# Sheet8.net
KiCad netlist of a schematic drawn in Altium Designer
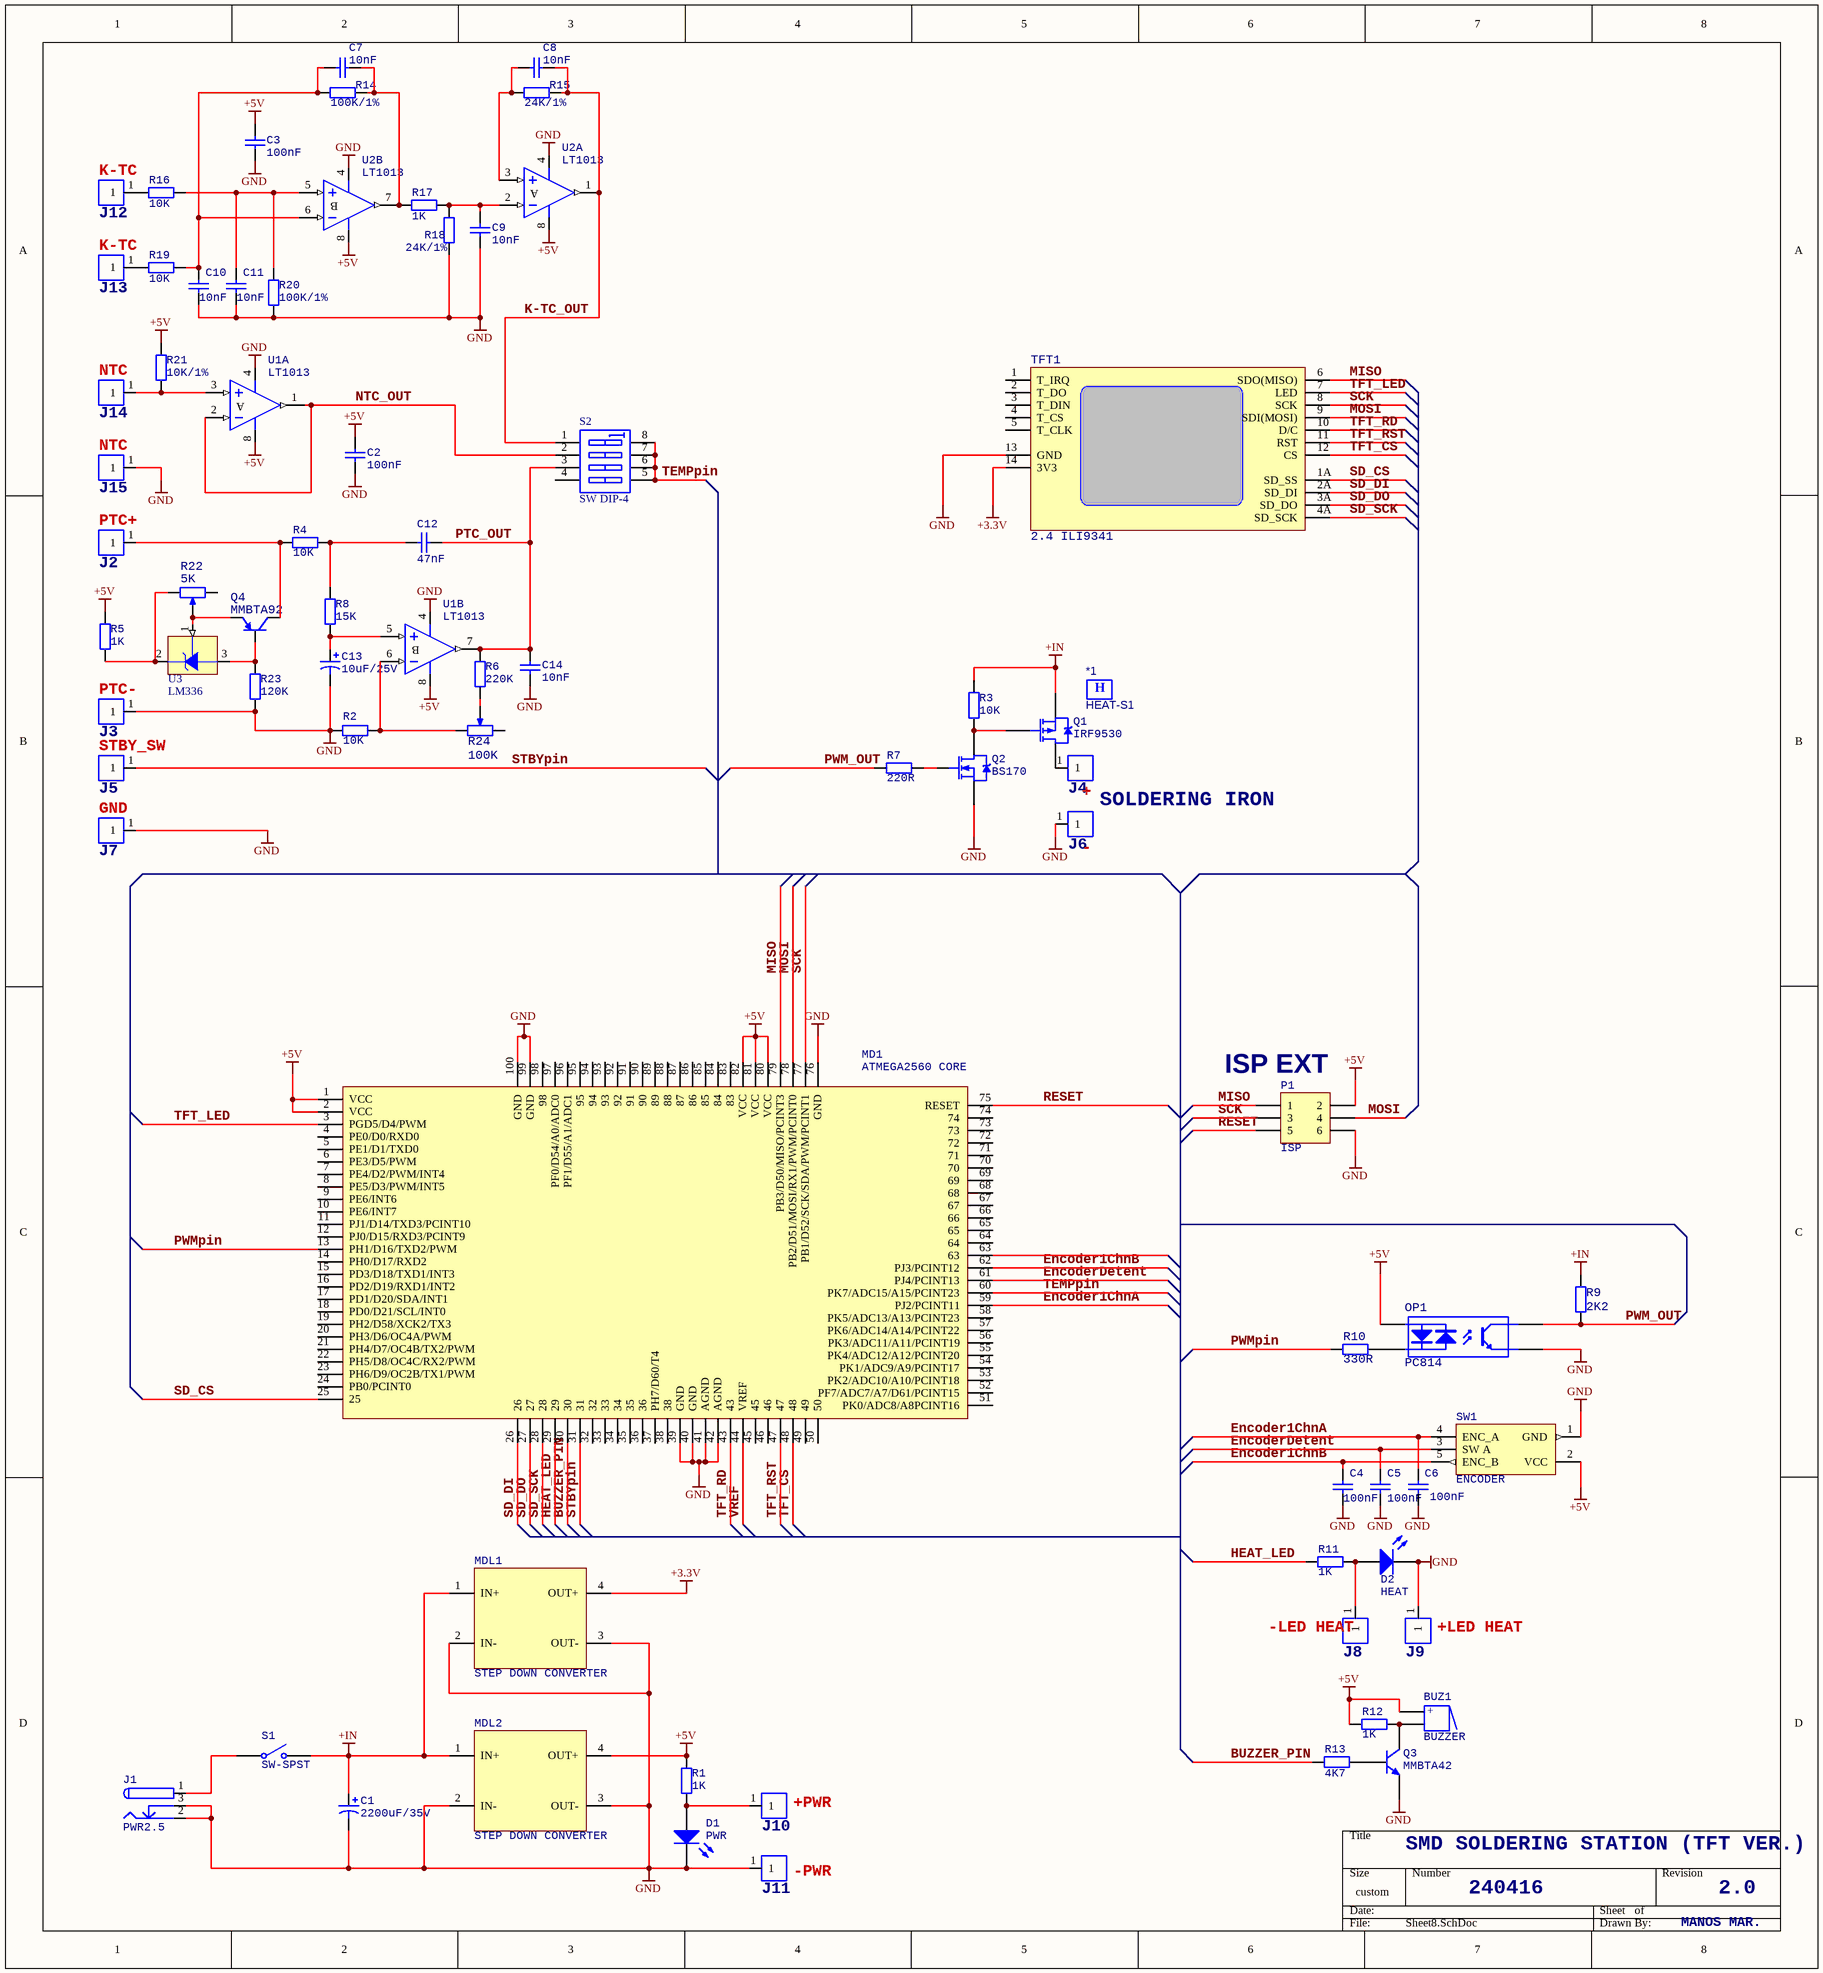
[diagram p0: Sheet8.SchDoc]

(export (version "E")
  (design (tool "Eeschema 10.0.6"))
  (components
    (comp (ref "*1")
      (value "HEAT-S1")
      (footprint "SK 104 HEATSHINK")
      (libsource (lib "SG_INTLIB") (part "HEAT-S1"))
    )
    (comp (ref "BUZ1") (value "BUZZER") (footprint "BUZZER") (libsource (lib "SMD STATION") (part "BUZZER")))
    (comp (ref "C1")
      (value "2200uF/35V")
      (footprint "RB5-10.5")
      (description "Polarized Capacitor (Radial)")
      (fields (field (name "PUBLISHER") "Altium Limited"))
      (libsource (lib "Miscellaneous Devices") (part "Cap Pol1"))
    )
    (comp (ref "C2")
      (value "100nF")
      (footprint "0805")
      (description "Capacitor, Ceramic, 4.7uF 10% 16V 0805 (2012) X7R")
      (fields (field (name "TOLERANCE") "10 %"))
      (libsource (lib "AltiumDesignLibrary") (part "CAP-NP"))
    )
    (comp (ref "C3")
      (value "100nF")
      (footprint "0805")
      (description "Capacitor, Ceramic, 4.7uF 10% 16V 0805 (2012) X7R")
      (fields (field (name "TOLERANCE") "10 %"))
      (libsource (lib "AltiumDesignLibrary") (part "CAP-NP"))
    )
    (comp (ref "C4")
      (value "100nF")
      (footprint "0805")
      (description "Capacitor")
      (fields (field (name "PUBLISHER") "Altium Limited"))
      (libsource (lib "Miscellaneous Devices") (part "Cap"))
    )
    (comp (ref "C5")
      (value "100nF")
      (footprint "0805")
      (description "Capacitor")
      (fields (field (name "PUBLISHER") "Altium Limited"))
      (libsource (lib "Miscellaneous Devices") (part "Cap"))
    )
    (comp (ref "C6")
      (value "100nF")
      (footprint "0805")
      (description "Capacitor")
      (fields (field (name "PUBLISHER") "Altium Limited"))
      (libsource (lib "Miscellaneous Devices") (part "Cap"))
    )
    (comp (ref "C7")
      (value "10nF")
      (footprint "0805")
      (description "Capacitor, Ceramic, 4.7uF 10% 16V 0805 (2012) X7R")
      (fields (field (name "TOLERANCE") "10 %"))
      (libsource (lib "AltiumDesignLibrary") (part "CAP-NP"))
    )
    (comp (ref "C8")
      (value "10nF")
      (footprint "0805")
      (description "Capacitor, Ceramic, 4.7uF 10% 16V 0805 (2012) X7R")
      (fields (field (name "TOLERANCE") "10 %"))
      (libsource (lib "AltiumDesignLibrary") (part "CAP-NP"))
    )
    (comp (ref "C9")
      (value "10nF")
      (footprint "0805")
      (description "Capacitor, Ceramic, 4.7uF 10% 16V 0805 (2012) X7R")
      (fields (field (name "TOLERANCE") "10 %"))
      (libsource (lib "AltiumDesignLibrary") (part "CAP-NP"))
    )
    (comp (ref "C10")
      (value "10nF")
      (footprint "0805")
      (description "Capacitor, Ceramic, 4.7uF 10% 16V 0805 (2012) X7R")
      (fields (field (name "TOLERANCE") "10 %"))
      (libsource (lib "AltiumDesignLibrary") (part "CAP-NP"))
    )
    (comp (ref "C11")
      (value "10nF")
      (footprint "0805")
      (description "Capacitor, Ceramic, 4.7uF 10% 16V 0805 (2012) X7R")
      (fields (field (name "TOLERANCE") "10 %"))
      (libsource (lib "AltiumDesignLibrary") (part "CAP-NP"))
    )
    (comp (ref "C12")
      (value "47nF")
      (footprint "0805")
      (description "Capacitor, Ceramic, 4.7uF 10% 16V 0805 (2012) X7R")
      (fields (field (name "TOLERANCE") "10 %"))
      (libsource (lib "AltiumDesignLibrary") (part "CAP-NP"))
    )
    (comp (ref "C13")
      (value "10uF/25V")
      (footprint "RB-08")
      (description "Polarized Capacitor (Radial)")
      (fields (field (name "PUBLISHER") "Altium Limited"))
      (libsource (lib "Miscellaneous Devices") (part "Cap Pol1"))
    )
    (comp (ref "C14")
      (value "10nF")
      (footprint "0805")
      (description "Capacitor, Ceramic, 4.7uF 10% 16V 0805 (2012) X7R")
      (fields (field (name "TOLERANCE") "10 %"))
      (libsource (lib "AltiumDesignLibrary") (part "CAP-NP"))
    )
    (comp (ref "D1")
      (value "PWR")
      (footprint "1206D")
      (description "Typical INFRARED GaAs LED")
      (fields (field (name "PUBLISHER") "Altium Limited"))
      (libsource (lib "Miscellaneous Devices") (part "LED0"))
    )
    (comp (ref "D2")
      (value "HEAT")
      (footprint "1206D")
      (description "Typical INFRARED GaAs LED")
      (fields (field (name "PUBLISHER") "Altium Limited"))
      (libsource (lib "Miscellaneous Devices") (part "LED0"))
    )
    (comp (ref "J1")
      (value "PWR2.5")
      (footprint "POWER JACK")
      (description "Low Voltage Power Supply Connector")
      (fields (field (name "PUBLISHER") "Altium Limited"))
      (libsource (lib "Miscellaneous Connectors") (part "PWR2.5"))
    )
    (comp (ref "J2")
      (value "PTC+")
      (footprint "CON2")
      (fields (field (name "MANUFACTURER") "Sta.Ge HELLAS"))
      (libsource (lib "Z_General_SCH_Library") (part "CON1_S"))
    )
    (comp (ref "J3")
      (value "PTC-")
      (footprint "CON2")
      (fields (field (name "MANUFACTURER") "Sta.Ge HELLAS"))
      (libsource (lib "Z_General_SCH_Library") (part "CON1_S"))
    )
    (comp (ref "J4")
      (value "+")
      (footprint "CON2")
      (fields (field (name "MANUFACTURER") "Sta.Ge HELLAS"))
      (libsource (lib "") (part "CON1_S_1"))
    )
    (comp (ref "J5")
      (value "STBY_SW")
      (footprint "CON2")
      (fields (field (name "MANUFACTURER") "Sta.Ge HELLAS"))
      (libsource (lib "Z_General_SCH_Library") (part "CON1_S"))
    )
    (comp (ref "J6")
      (value "-")
      (footprint "CON2")
      (fields (field (name "MANUFACTURER") "Sta.Ge HELLAS"))
      (libsource (lib "") (part "CON1_S_1"))
    )
    (comp (ref "J7")
      (value "GND")
      (footprint "CON2")
      (fields (field (name "MANUFACTURER") "Sta.Ge HELLAS"))
      (libsource (lib "Z_General_SCH_Library") (part "CON1_S"))
    )
    (comp (ref "J8")
      (value "-LED HEAT")
      (footprint "CON2")
      (fields (field (name "MANUFACTURER") "Sta.Ge HELLAS"))
      (libsource (lib "") (part "CON1_S_2"))
    )
    (comp (ref "J9")
      (value "+LED HEAT")
      (footprint "CON2")
      (fields (field (name "MANUFACTURER") "Sta.Ge HELLAS"))
      (libsource (lib "") (part "CON1_S_2"))
    )
    (comp (ref "J10")
      (value "+PWR")
      (footprint "CON2")
      (fields (field (name "MANUFACTURER") "Sta.Ge HELLAS"))
      (libsource (lib "") (part "CON1_S_1"))
    )
    (comp (ref "J11")
      (value "-PWR")
      (footprint "CON2")
      (fields (field (name "MANUFACTURER") "Sta.Ge HELLAS"))
      (libsource (lib "") (part "CON1_S_1"))
    )
    (comp (ref "J12")
      (value "K-TC")
      (footprint "CON2")
      (fields (field (name "MANUFACTURER") "Sta.Ge HELLAS"))
      (libsource (lib "Z_General_SCH_Library") (part "CON1_S"))
    )
    (comp (ref "J13")
      (value "K-TC")
      (footprint "CON2")
      (fields (field (name "MANUFACTURER") "Sta.Ge HELLAS"))
      (libsource (lib "Z_General_SCH_Library") (part "CON1_S"))
    )
    (comp (ref "J14")
      (value "NTC")
      (footprint "CON2")
      (fields (field (name "MANUFACTURER") "Sta.Ge HELLAS"))
      (libsource (lib "Z_General_SCH_Library") (part "CON1_S"))
    )
    (comp (ref "J15")
      (value "NTC")
      (footprint "CON2")
      (fields (field (name "MANUFACTURER") "Sta.Ge HELLAS"))
      (libsource (lib "Z_General_SCH_Library") (part "CON1_S"))
    )
    (comp (ref "MD1")
      (value "ATMEGA2560 CORE")
      (footprint "ATMEGA 2560 CORE")
      (libsource (lib "SMD STATION") (part "ATMEGA2560 CORE"))
    )
    (comp (ref "MDL1")
      (value "STEP DOWN CONVERTER")
      (footprint "STEP DOWN CONVERTER MINI")
      (libsource (lib "SMD STATION") (part "STEP DOWN CONVERTER"))
    )
    (comp (ref "MDL2")
      (value "STEP DOWN CONVERTER")
      (footprint "STEP DOWN CONVERTER MINI")
      (libsource (lib "SMD STATION") (part "STEP DOWN CONVERTER"))
    )
    (comp (ref "OP1")
      (value "PC814")
      (footprint "SOP-4")
      (description "AC OPTOCUPLER")
      (libsource (lib "STAGE_MP3") (part "OPTO-AC1"))
    )
    (comp (ref "P1")
      (value "ISP")
      (footprint "HDR2X3")
      (description "Header, 3-Pin, Dual row")
      (fields (field (name "PUBLISHER") "Altium Limited"))
      (libsource (lib "Miscellaneous Connectors") (part "Header 3X2"))
    )
    (comp (ref "Q1")
      (value "IRF9530")
      (footprint "TO-220V")
      (description "P-Channel Power MOSFET")
      (fields (field (name "PUBLISHER") "Altium Limited"))
      (libsource (lib "Miscellaneous Devices") (part "PMOS-2"))
    )
    (comp (ref "Q2")
      (value "BS170")
      (footprint "T0-92")
      (description "N-Channel Power MOSFET")
      (fields (field (name "PUBLISHER") "Altium Limited"))
      (libsource (lib "Miscellaneous Devices") (part "NMOS-2"))
    )
    (comp (ref "Q3")
      (value "MMBTA42")
      (footprint "SO-G3")
      (description "NPN Bipolar Transistor")
      (fields (field (name "PUBLISHER") "Altium Limited"))
      (libsource (lib "Miscellaneous Devices") (part "NPN"))
    )
    (comp (ref "Q4")
      (value "MMBTA92")
      (footprint "SO-G3")
      (description "PNP Bipolar Transistor")
      (fields (field (name "PUBLISHER") "Altium Limited"))
      (libsource (lib "Miscellaneous Devices") (part "PNP"))
    )
    (comp (ref "R1")
      (value "1K")
      (footprint "0805")
      (description "Resistor")
      (fields (field (name "PUBLISHER") "Altium Limited"))
      (libsource (lib "") (part "Res2_1"))
    )
    (comp (ref "R2")
      (value "10K")
      (footprint "0805")
      (fields
        (field (name "MANUFACTURER") "Generic Components")
        (field (name "POWER") "0,2W")
        (field (name "SGPARTNUMBER") "R001051")
        (field (name "PUBLISHER") "Altium Limited")
      )
      (libsource (lib "SG_PCB") (part "RES"))
    )
    (comp (ref "R3")
      (value "10K")
      (footprint "0805")
      (description "Resistor")
      (fields (field (name "PUBLISHER") "Altium Limited"))
      (libsource (lib "") (part "Res2_1"))
    )
    (comp (ref "R4")
      (value "10K")
      (footprint "0805")
      (fields
        (field (name "MANUFACTURER") "Generic Components")
        (field (name "POWER") "0,2W")
        (field (name "SGPARTNUMBER") "R001051")
        (field (name "PUBLISHER") "Altium Limited")
      )
      (libsource (lib "") (part "RES_2"))
    )
    (comp (ref "R5")
      (value "1K")
      (footprint "0805")
      (fields
        (field (name "MANUFACTURER") "Generic Components")
        (field (name "POWER") "0,2W")
        (field (name "SGPARTNUMBER") "R001051")
        (field (name "PUBLISHER") "Altium Limited")
      )
      (libsource (lib "") (part "RES_3"))
    )
    (comp (ref "R6")
      (value "220K")
      (footprint "0805")
      (fields
        (field (name "MANUFACTURER") "Generic Components")
        (field (name "POWER") "0,2W")
        (field (name "SGPARTNUMBER") "R001051")
        (field (name "PUBLISHER") "Altium Limited")
      )
      (libsource (lib "") (part "RES_1"))
    )
    (comp (ref "R7")
      (value "220R")
      (footprint "0805")
      (description "Resistor")
      (fields (field (name "PUBLISHER") "Altium Limited"))
      (libsource (lib "Miscellaneous Devices") (part "Res2"))
    )
    (comp (ref "R8")
      (value "15K")
      (footprint "0805")
      (fields
        (field (name "MANUFACTURER") "Generic Components")
        (field (name "POWER") "0,2W")
        (field (name "SGPARTNUMBER") "R001051")
        (field (name "PUBLISHER") "Altium Limited")
      )
      (libsource (lib "") (part "RES_1"))
    )
    (comp (ref "R9")
      (value "2K2")
      (footprint "0805")
      (fields
        (field (name "MANUFACTURER") "Generic Components")
        (field (name "POWER") "0,2W")
        (field (name "SGPARTNUMBER") "R001051")
        (field (name "PUBLISHER") "Altium Limited")
      )
      (libsource (lib "") (part "RES_1"))
    )
    (comp (ref "R10")
      (value "330R")
      (footprint "0805")
      (fields
        (field (name "MANUFACTURER") "Generic Components")
        (field (name "POWER") "0,2W")
        (field (name "SGPARTNUMBER") "R001051")
        (field (name "PUBLISHER") "Altium Limited")
      )
      (libsource (lib "SG_PCB") (part "RES"))
    )
    (comp (ref "R11")
      (value "1K")
      (footprint "0805")
      (description "Resistor")
      (fields (field (name "PUBLISHER") "Altium Limited"))
      (libsource (lib "Miscellaneous Devices") (part "Res2"))
    )
    (comp (ref "R12")
      (value "1K")
      (footprint "0805")
      (fields
        (field (name "MANUFACTURER") "Generic Components")
        (field (name "POWER") "0,2W")
        (field (name "SGPARTNUMBER") "R001051")
        (field (name "PUBLISHER") "Altium Limited")
      )
      (libsource (lib "SG_PCB") (part "RES"))
    )
    (comp (ref "R13")
      (value "4K7")
      (footprint "0805")
      (fields
        (field (name "MANUFACTURER") "Generic Components")
        (field (name "POWER") "0,2W")
        (field (name "SGPARTNUMBER") "R001051")
        (field (name "PUBLISHER") "Altium Limited")
      )
      (libsource (lib "") (part "RES_2"))
    )
    (comp (ref "R14")
      (value "100K/1%")
      (footprint "0805")
      (fields
        (field (name "MANUFACTURER") "Generic Components")
        (field (name "POWER") "0,2W")
        (field (name "SGPARTNUMBER") "R001051")
        (field (name "PUBLISHER") "Altium Limited")
      )
      (libsource (lib "SG_PCB") (part "RES"))
    )
    (comp (ref "R15")
      (value "24K/1%")
      (footprint "0805")
      (fields
        (field (name "MANUFACTURER") "Generic Components")
        (field (name "POWER") "0,2W")
        (field (name "SGPARTNUMBER") "R001051")
        (field (name "PUBLISHER") "Altium Limited")
      )
      (libsource (lib "SG_PCB") (part "RES"))
    )
    (comp (ref "R16")
      (value "10K")
      (footprint "0805")
      (fields
        (field (name "MANUFACTURER") "Generic Components")
        (field (name "POWER") "0,2W")
        (field (name "SGPARTNUMBER") "R001051")
        (field (name "PUBLISHER") "Altium Limited")
      )
      (libsource (lib "SG_PCB") (part "RES"))
    )
    (comp (ref "R17")
      (value "1K")
      (footprint "0805")
      (fields
        (field (name "MANUFACTURER") "Generic Components")
        (field (name "POWER") "0,2W")
        (field (name "SGPARTNUMBER") "R001051")
        (field (name "PUBLISHER") "Altium Limited")
      )
      (libsource (lib "SG_PCB") (part "RES"))
    )
    (comp (ref "R18")
      (value "24K/1%")
      (footprint "0805")
      (fields
        (field (name "MANUFACTURER") "Generic Components")
        (field (name "POWER") "0,2W")
        (field (name "SGPARTNUMBER") "R001051")
        (field (name "PUBLISHER") "Altium Limited")
      )
      (libsource (lib "") (part "RES_1"))
    )
    (comp (ref "R19")
      (value "10K")
      (footprint "0805")
      (fields
        (field (name "MANUFACTURER") "Generic Components")
        (field (name "POWER") "0,2W")
        (field (name "SGPARTNUMBER") "R001051")
        (field (name "PUBLISHER") "Altium Limited")
      )
      (libsource (lib "SG_PCB") (part "RES"))
    )
    (comp (ref "R20")
      (value "100K/1%")
      (footprint "0805")
      (fields
        (field (name "MANUFACTURER") "Generic Components")
        (field (name "POWER") "0,2W")
        (field (name "SGPARTNUMBER") "R001051")
        (field (name "PUBLISHER") "Altium Limited")
      )
      (libsource (lib "") (part "RES_3"))
    )
    (comp (ref "R21")
      (value "10K/1%")
      (footprint "0805")
      (fields
        (field (name "MANUFACTURER") "Generic Components")
        (field (name "POWER") "0,2W")
        (field (name "SGPARTNUMBER") "R001051")
        (field (name "PUBLISHER") "Altium Limited")
      )
      (libsource (lib "AVR SMD SOLDERING") (part "RES"))
    )
    (comp (ref "R22")
      (value "5K")
      (footprint "VR6")
      (fields
        (field (name "MANUFACTURER") "Sta.Ge HELLAS")
        (field (name "SGPARTNUMBER") "R001049")
        (field (name "PART NUMBER") "R002107")
        (field (name "PUBLISHER") "Altium Limited")
      )
      (libsource (lib "") (part "RPot2_1"))
    )
    (comp (ref "R23")
      (value "120K")
      (footprint "0805")
      (fields
        (field (name "MANUFACTURER") "Generic Components")
        (field (name "POWER") "0,2W")
        (field (name "SGPARTNUMBER") "R001051")
        (field (name "PUBLISHER") "Altium Limited")
      )
      (libsource (lib "") (part "RES_3"))
    )
    (comp (ref "R24")
      (value "100K")
      (footprint "VR6")
      (fields
        (field (name "MANUFACTURER") "Sta.Ge HELLAS")
        (field (name "SGPARTNUMBER") "R001049")
        (field (name "PART NUMBER") "R002107")
        (field (name "PUBLISHER") "Altium Limited")
      )
      (libsource (lib "SG_INTLIB") (part "RPot2"))
    )
    (comp (ref "S1")
      (value "SW-SPST")
      (footprint "SPST-2")
      (description "Single-Pole, Single-Throw Switch")
      (fields (field (name "PUBLISHER") "Altium Limited"))
      (libsource (lib "Miscellaneous Devices") (part "SW-SPST"))
    )
    (comp (ref "S2")
      (value "SW DIP-4")
      (footprint "DIP-8")
      (description "DIP Switch, 4 Position, SPST")
      (fields (field (name "PUBLISHER") "Altium Limited"))
      (libsource (lib "Miscellaneous Devices") (part "SW DIP-4"))
    )
    (comp (ref "SW1")
      (value "ENCODER")
      (footprint "HDR1X5")
      (libsource (lib "SMD STATION") (part "ROTARY ENC"))
    )
    (comp (ref "TFT1")
      (value "2.4 ILI9341")
      (footprint "Miscellaneous Connectors:HDR1X18")
      (libsource (lib "SMD STATION") (part "2.4 TFT"))
    )
    (comp (ref "U1")
      (value "LT1013")
      (footprint "DIP-8")
      (description "Dual Precision Operational Amplifier")
      (fields (field (name "PUBLISHER") "Altium Limited"))
      (libsource (lib "LT Operational Amplifier") (part "LT1013ACJ8"))
    )
    (comp (ref "U2")
      (value "LT1013")
      (footprint "DIP-8")
      (description "Dual Precision Operational Amplifier")
      (fields (field (name "PUBLISHER") "Altium Limited"))
      (libsource (lib "LT Operational Amplifier") (part "LT1013ACJ8"))
    )
    (comp (ref "U3")
      (value "LM336")
      (footprint "Z03A")
      (description "Adjustable Micropower Voltage Reference")
      (fields (field (name "PUBLISHER") "Altium Limited"))
      (libsource (lib "NSC Power Mgt Voltage Reference") (part "LM385Z"))
    )
  )
  (nets
    (net (code "1") (name "+3.3V") (class "Default")
      (node (ref "MDL1") (pin "4") (pinfunction "OUT+_4") (pintype "passive"))
      (node (ref "TFT1") (pin "14") (pinfunction "3V3_14") (pintype "passive"))
    )
    (net (code "2") (name "+5V") (class "Default")
      (node (ref "BUZ1") (pin "1") (pinfunction "1_1") (pintype "passive"))
      (node (ref "C2") (pin "2") (pinfunction "2_2") (pintype "passive"))
      (node (ref "C3") (pin "2") (pinfunction "2_2") (pintype "passive"))
      (node (ref "MD1") (pin "1") (pinfunction "VCC_1") (pintype "passive"))
      (node (ref "MD1") (pin "2") (pinfunction "VCC_2") (pintype "passive"))
      (node (ref "MD1") (pin "80") (pinfunction "VCC_80") (pintype "passive"))
      (node (ref "MD1") (pin "81") (pinfunction "VCC_81") (pintype "passive"))
      (node (ref "MD1") (pin "82") (pinfunction "VCC_82") (pintype "passive"))
      (node (ref "MDL2") (pin "4") (pinfunction "OUT+_4") (pintype "passive"))
      (node (ref "OP1") (pin "1") (pinfunction "A_1") (pintype "passive"))
      (node (ref "P1") (pin "2") (pinfunction "2_2") (pintype "passive"))
      (node (ref "R1") (pin "2") (pinfunction "2_2") (pintype "passive"))
      (node (ref "R12") (pin "2") (pinfunction "2_2") (pintype "passive"))
      (node (ref "R21") (pin "2") (pinfunction "2_2") (pintype "passive"))
      (node (ref "R5") (pin "2") (pinfunction "2_2") (pintype "passive"))
      (node (ref "SW1") (pin "2") (pinfunction "VCC_2") (pintype "passive"))
      (node (ref "U1") (pin "8") (pinfunction "V+_8") (pintype "power_in"))
      (node (ref "U2") (pin "8") (pinfunction "V+_8") (pintype "power_in"))
    )
    (net (code "3") (name "+IN") (class "Default")
      (node (ref "C1") (pin "1") (pinfunction "1_1") (pintype "passive"))
      (node (ref "MDL1") (pin "1") (pinfunction "IN+_1") (pintype "passive"))
      (node (ref "MDL2") (pin "1") (pinfunction "IN+_1") (pintype "passive"))
      (node (ref "Q1") (pin "3") (pinfunction "S_3") (pintype "passive"))
      (node (ref "R3") (pin "2") (pinfunction "2_2") (pintype "passive"))
      (node (ref "R9") (pin "1") (pinfunction "1_1") (pintype "passive"))
      (node (ref "S1") (pin "2") (pinfunction "NO_2") (pintype "passive"))
    )
    (net (code "4") (name "/BUZZER_PIN") (class "Default")
      (node (ref "MD1") (pin "30") (pinfunction "30_30") (pintype "passive"))
      (node (ref "R13") (pin "1") (pinfunction "1_1") (pintype "passive"))
    )
    (net (code "5") (name "/Encoder1ChnA") (class "Default")
      (node (ref "C6") (pin "1") (pinfunction "1_1") (pintype "passive"))
      (node (ref "MD1") (pin "59") (pinfunction "PJ2/PCINT11_59") (pintype "passive"))
      (node (ref "SW1") (pin "4") (pinfunction "ENC_A_4") (pintype "passive"))
    )
    (net (code "6") (name "/Encoder1ChnB") (class "Default")
      (node (ref "C4") (pin "1") (pinfunction "1_1") (pintype "passive"))
      (node (ref "MD1") (pin "62") (pinfunction "PJ3/PCINT12_62") (pintype "passive"))
      (node (ref "SW1") (pin "5") (pinfunction "ENC_B_5") (pintype "output"))
    )
    (net (code "7") (name "/EncoderDetent") (class "Default")
      (node (ref "C5") (pin "1") (pinfunction "1_1") (pintype "passive"))
      (node (ref "MD1") (pin "61") (pinfunction "PJ4/PCINT13_61") (pintype "passive"))
      (node (ref "SW1") (pin "3") (pinfunction "SW_A_3") (pintype "passive"))
    )
    (net (code "8") (name "/HEAT_LED") (class "Default")
      (node (ref "MD1") (pin "29") (pinfunction "29_29") (pintype "passive"))
      (node (ref "R11") (pin "1") (pinfunction "1_1") (pintype "passive"))
    )
    (net (code "9") (name "/K-TC_OUT") (class "Default")
      (node (ref "C8") (pin "1") (pinfunction "1_1") (pintype "passive"))
      (node (ref "R15") (pin "1") (pinfunction "1_1") (pintype "passive"))
      (node (ref "S2") (pin "1") (pinfunction "A1_1") (pintype "passive"))
      (node (ref "U2") (pin "1") (pinfunction "OUT_1") (pintype "output"))
    )
    (net (code "10") (name "/MISO") (class "Default")
      (node (ref "MD1") (pin "79") (pinfunction "PB3/D50/MISO/PCINT3_79") (pintype "passive"))
      (node (ref "P1") (pin "1") (pinfunction "1_1") (pintype "passive"))
      (node (ref "TFT1") (pin "6") (pinfunction "SDO(MISO)_6") (pintype "passive"))
    )
    (net (code "11") (name "/MOSI") (class "Default")
      (node (ref "MD1") (pin "78") (pinfunction "PB2/D51/MOSI/RX1/PWM/PCINT0_78") (pintype "passive"))
      (node (ref "P1") (pin "4") (pinfunction "4_4") (pintype "passive"))
      (node (ref "TFT1") (pin "9") (pinfunction "SDI(MOSI)_9") (pintype "passive"))
    )
    (net (code "12") (name "/NTC_OUT") (class "Default")
      (node (ref "S2") (pin "2") (pinfunction "A2_2") (pintype "passive"))
      (node (ref "U1") (pin "1") (pinfunction "OUT_1") (pintype "output"))
      (node (ref "U1") (pin "2") (pinfunction "IN-_2") (pintype "input"))
    )
    (net (code "13") (name "/PTC_OUT") (class "Default")
      (node (ref "C12") (pin "1") (pinfunction "1_1") (pintype "passive"))
      (node (ref "C14") (pin "2") (pinfunction "2_2") (pintype "passive"))
      (node (ref "R6") (pin "1") (pinfunction "1_1") (pintype "passive"))
      (node (ref "S2") (pin "3") (pinfunction "A3_3") (pintype "passive"))
      (node (ref "U1") (pin "7") (pinfunction "OUT_7") (pintype "output"))
    )
    (net (code "14") (name "/PWM_OUT") (class "Default")
      (node (ref "OP1") (pin "4") (pinfunction "C_4") (pintype "passive"))
      (node (ref "R7") (pin "1") (pinfunction "1_1") (pintype "passive"))
      (node (ref "R9") (pin "2") (pinfunction "2_2") (pintype "passive"))
    )
    (net (code "15") (name "/PWMpin") (class "Default")
      (node (ref "MD1") (pin "13") (pinfunction "PH1/D16/TXD2/PWM_13") (pintype "passive"))
      (node (ref "R10") (pin "2") (pinfunction "2_2") (pintype "passive"))
    )
    (net (code "16") (name "/RESET") (class "Default")
      (node (ref "MD1") (pin "75") (pinfunction "RESET_75") (pintype "passive"))
      (node (ref "P1") (pin "5") (pinfunction "5_5") (pintype "passive"))
    )
    (net (code "17") (name "/SCK") (class "Default")
      (node (ref "MD1") (pin "77") (pinfunction "PB1/D52/SCK/SDA/PWM/PCINT1_77") (pintype "passive"))
      (node (ref "P1") (pin "3") (pinfunction "3_3") (pintype "passive"))
      (node (ref "TFT1") (pin "8") (pinfunction "SCK_8") (pintype "passive"))
    )
    (net (code "18") (name "/SD_CS") (class "Default")
      (node (ref "MD1") (pin "25") (pinfunction "25_25") (pintype "passive"))
      (node (ref "TFT1") (pin "1A") (pinfunction "SD_SS_1A") (pintype "passive"))
    )
    (net (code "19") (name "/SD_DI") (class "Default")
      (node (ref "MD1") (pin "26") (pinfunction "26_26") (pintype "passive"))
      (node (ref "TFT1") (pin "2A") (pinfunction "SD_DI_2A") (pintype "passive"))
    )
    (net (code "20") (name "/SD_DO") (class "Default")
      (node (ref "MD1") (pin "27") (pinfunction "27_27") (pintype "passive"))
      (node (ref "TFT1") (pin "3A") (pinfunction "SD_DO_3A") (pintype "passive"))
    )
    (net (code "21") (name "/SD_SCK") (class "Default")
      (node (ref "MD1") (pin "28") (pinfunction "28_28") (pintype "passive"))
      (node (ref "TFT1") (pin "4A") (pinfunction "SD_SCK_4A") (pintype "passive"))
    )
    (net (code "22") (name "/STBYpin") (class "Default")
      (node (ref "J5") (pin "1") (pinfunction "1_1") (pintype "passive"))
      (node (ref "MD1") (pin "31") (pinfunction "31_31") (pintype "passive"))
    )
    (net (code "23") (name "/TEMPpin") (class "Default")
      (node (ref "MD1") (pin "60") (pinfunction "PK7/ADC15/A15/PCINT23_60") (pintype "passive"))
      (node (ref "S2") (pin "5") (pinfunction "B4_5") (pintype "passive"))
      (node (ref "S2") (pin "6") (pinfunction "B3_6") (pintype "passive"))
      (node (ref "S2") (pin "7") (pinfunction "B2_7") (pintype "passive"))
      (node (ref "S2") (pin "8") (pinfunction "B1_8") (pintype "passive"))
    )
    (net (code "24") (name "/TFT_CS") (class "Default")
      (node (ref "MD1") (pin "48") (pinfunction "48_48") (pintype "passive"))
      (node (ref "TFT1") (pin "12") (pinfunction "CS_12") (pintype "passive"))
    )
    (net (code "25") (name "/TFT_LED") (class "Default")
      (node (ref "MD1") (pin "3") (pinfunction "PGD5/D4/PWM_3") (pintype "passive"))
      (node (ref "TFT1") (pin "7") (pinfunction "LED_7") (pintype "passive"))
    )
    (net (code "26") (name "/TFT_RD") (class "Default")
      (node (ref "MD1") (pin "43") (pinfunction "43_43") (pintype "passive"))
      (node (ref "TFT1") (pin "10") (pinfunction "D/C_10") (pintype "passive"))
    )
    (net (code "27") (name "/TFT_RST") (class "Default")
      (node (ref "MD1") (pin "47") (pinfunction "47_47") (pintype "passive"))
      (node (ref "TFT1") (pin "11") (pinfunction "RST_11") (pintype "passive"))
    )
    (net (code "28") (name "/VREF") (class "Default")
      (node (ref "MD1") (pin "44") (pinfunction "VREF_44") (pintype "passive"))
    )
    (net (code "29") (name "GND") (class "Default")
      (node (ref "C1") (pin "2") (pinfunction "2_2") (pintype "passive"))
      (node (ref "C10") (pin "1") (pinfunction "1_1") (pintype "passive"))
      (node (ref "C11") (pin "1") (pinfunction "1_1") (pintype "passive"))
      (node (ref "C13") (pin "2") (pinfunction "2_2") (pintype "passive"))
      (node (ref "C14") (pin "1") (pinfunction "1_1") (pintype "passive"))
      (node (ref "C2") (pin "1") (pinfunction "1_1") (pintype "passive"))
      (node (ref "C3") (pin "1") (pinfunction "1_1") (pintype "passive"))
      (node (ref "C4") (pin "2") (pinfunction "2_2") (pintype "passive"))
      (node (ref "C5") (pin "2") (pinfunction "2_2") (pintype "passive"))
      (node (ref "C6") (pin "2") (pinfunction "2_2") (pintype "passive"))
      (node (ref "C9") (pin "2") (pinfunction "2_2") (pintype "passive"))
      (node (ref "D1") (pin "2") (pinfunction "K_2") (pintype "passive"))
      (node (ref "D2") (pin "2") (pinfunction "K_2") (pintype "passive"))
      (node (ref "J1") (pin "2") (pinfunction "2_2") (pintype "power_in"))
      (node (ref "J1") (pin "3") (pinfunction "3_3") (pintype "power_in"))
      (node (ref "J11") (pin "1") (pinfunction "1_1") (pintype "passive"))
      (node (ref "J15") (pin "1") (pinfunction "1_1") (pintype "passive"))
      (node (ref "J3") (pin "1") (pinfunction "1_1") (pintype "passive"))
      (node (ref "J6") (pin "1") (pinfunction "1_1") (pintype "passive"))
      (node (ref "J7") (pin "1") (pinfunction "1_1") (pintype "passive"))
      (node (ref "J9") (pin "1") (pinfunction "1_1") (pintype "passive"))
      (node (ref "MD1") (pin "100") (pinfunction "GND_100") (pintype "passive"))
      (node (ref "MD1") (pin "39") (pinfunction "GND_39") (pintype "passive"))
      (node (ref "MD1") (pin "40") (pinfunction "GND_40") (pintype "passive"))
      (node (ref "MD1") (pin "41") (pinfunction "AGND_41") (pintype "passive"))
      (node (ref "MD1") (pin "42") (pinfunction "AGND_42") (pintype "passive"))
      (node (ref "MD1") (pin "76") (pinfunction "GND_76") (pintype "passive"))
      (node (ref "MD1") (pin "99") (pinfunction "GND_99") (pintype "passive"))
      (node (ref "MDL1") (pin "2") (pinfunction "IN-_2") (pintype "passive"))
      (node (ref "MDL1") (pin "3") (pinfunction "OUT-_3") (pintype "passive"))
      (node (ref "MDL2") (pin "2") (pinfunction "IN-_2") (pintype "passive"))
      (node (ref "MDL2") (pin "3") (pinfunction "OUT-_3") (pintype "passive"))
      (node (ref "OP1") (pin "3") (pinfunction "E_3") (pintype "passive"))
      (node (ref "P1") (pin "6") (pinfunction "6_6") (pintype "passive"))
      (node (ref "Q2") (pin "3") (pinfunction "S_3") (pintype "passive"))
      (node (ref "Q3") (pin "2") (pinfunction "E_2") (pintype "passive"))
      (node (ref "R18") (pin "2") (pinfunction "2_2") (pintype "passive"))
      (node (ref "R2") (pin "2") (pinfunction "2_2") (pintype "passive"))
      (node (ref "R20") (pin "1") (pinfunction "1_1") (pintype "passive"))
      (node (ref "R23") (pin "1") (pinfunction "1_1") (pintype "passive"))
      (node (ref "SW1") (pin "1") (pinfunction "GND_1") (pintype "output"))
      (node (ref "TFT1") (pin "13") (pinfunction "GND_13") (pintype "passive"))
      (node (ref "U1") (pin "4") (pinfunction "V-_4") (pintype "power_in"))
      (node (ref "U2") (pin "4") (pinfunction "V-_4") (pintype "power_in"))
    )
    (net (code "30") (name "Net-(C12-Pad2)") (class "Default")
      (node (ref "C12") (pin "2") (pinfunction "2_2") (pintype "passive"))
      (node (ref "R4") (pin "2") (pinfunction "2_2") (pintype "passive"))
      (node (ref "R8") (pin "1") (pinfunction "1_1") (pintype "passive"))
    )
    (net (code "31") (name "Net-(D1-A)") (class "Default")
      (node (ref "D1") (pin "1") (pinfunction "A_1") (pintype "passive"))
      (node (ref "J10") (pin "1") (pinfunction "1_1") (pintype "passive"))
      (node (ref "R1") (pin "1") (pinfunction "1_1") (pintype "passive"))
    )
    (net (code "32") (name "Net-(D2-A)") (class "Default")
      (node (ref "D2") (pin "1") (pinfunction "A_1") (pintype "passive"))
      (node (ref "J8") (pin "1") (pinfunction "1_1") (pintype "passive"))
      (node (ref "R11") (pin "2") (pinfunction "2_2") (pintype "passive"))
    )
    (net (code "33") (name "Net-(J12-Pad1)") (class "Default")
      (node (ref "J12") (pin "1") (pinfunction "1_1") (pintype "passive"))
      (node (ref "R16") (pin "2") (pinfunction "2_2") (pintype "passive"))
    )
    (net (code "34") (name "Net-(J13-Pad1)") (class "Default")
      (node (ref "J13") (pin "1") (pinfunction "1_1") (pintype "passive"))
      (node (ref "R19") (pin "2") (pinfunction "2_2") (pintype "passive"))
    )
    (net (code "35") (name "Net-(OP1-K)") (class "Default")
      (node (ref "OP1") (pin "2") (pinfunction "K_2") (pintype "passive"))
      (node (ref "R10") (pin "1") (pinfunction "1_1") (pintype "passive"))
    )
    (net (code "36") (name "Net-(Q1-D)") (class "Default")
      (node (ref "J4") (pin "1") (pinfunction "1_1") (pintype "passive"))
      (node (ref "Q1") (pin "2") (pinfunction "D_2") (pintype "passive"))
    )
    (net (code "37") (name "Net-(Q1-G)") (class "Default")
      (node (ref "Q1") (pin "1") (pinfunction "G_1") (pintype "passive"))
      (node (ref "Q2") (pin "2") (pinfunction "D_2") (pintype "passive"))
      (node (ref "R3") (pin "1") (pinfunction "1_1") (pintype "passive"))
    )
    (net (code "38") (name "Net-(Q2-G)") (class "Default")
      (node (ref "Q2") (pin "1") (pinfunction "G_1") (pintype "passive"))
      (node (ref "R7") (pin "2") (pinfunction "2_2") (pintype "passive"))
    )
    (net (code "39") (name "Net-(Q3-B)") (class "Default")
      (node (ref "Q3") (pin "1") (pinfunction "B_1") (pintype "passive"))
      (node (ref "R13") (pin "2") (pinfunction "2_2") (pintype "passive"))
    )
    (net (code "40") (name "Net-(Q3-C)") (class "Default")
      (node (ref "BUZ1") (pin "2") (pinfunction "2_2") (pintype "passive"))
      (node (ref "Q3") (pin "3") (pinfunction "C_3") (pintype "passive"))
      (node (ref "R12") (pin "1") (pinfunction "1_1") (pintype "passive"))
    )
    (net (code "41") (name "Net-(Q4-B)") (class "Default")
      (node (ref "Q4") (pin "1") (pinfunction "B_1") (pintype "passive"))
      (node (ref "R23") (pin "2") (pinfunction "2_2") (pintype "passive"))
      (node (ref "U3") (pin "3") (pinfunction "-V_3") (pintype "passive"))
    )
    (net (code "42") (name "Net-(Q4-C)") (class "Default")
      (node (ref "J2") (pin "1") (pinfunction "1_1") (pintype "passive"))
      (node (ref "Q4") (pin "3") (pinfunction "C_3") (pintype "passive"))
      (node (ref "R4") (pin "1") (pinfunction "1_1") (pintype "passive"))
    )
    (net (code "43") (name "Net-(Q4-E)") (class "Default")
      (node (ref "Q4") (pin "2") (pinfunction "E_2") (pintype "passive"))
      (node (ref "R22") (pin "2") (pinfunction "TAP_2") (pintype "passive"))
      (node (ref "U3") (pin "1") (pinfunction "ADJ_1") (pintype "input"))
    )
    (net (code "44") (name "Net-(R22-TOP)") (class "Default")
      (node (ref "R22") (pin "1") (pinfunction "TOP_1") (pintype "passive"))
      (node (ref "R5") (pin "1") (pinfunction "1_1") (pintype "passive"))
      (node (ref "U3") (pin "2") (pinfunction "+V_2") (pintype "passive"))
    )
    (net (code "45") (name "Net-(R24-BOT)") (class "Default")
      (node (ref "R2") (pin "1") (pinfunction "1_1") (pintype "passive"))
      (node (ref "R24") (pin "1") (pinfunction "BOT_1") (pintype "passive"))
      (node (ref "U1") (pin "6") (pinfunction "IN-_6") (pintype "input"))
    )
    (net (code "46") (name "Net-(R24-TAP)") (class "Default")
      (node (ref "R24") (pin "2") (pinfunction "TAP_2") (pintype "passive"))
      (node (ref "R6") (pin "2") (pinfunction "2_2") (pintype "passive"))
    )
    (net (code "47") (name "Net-(S1-COMMON)") (class "Default")
      (node (ref "J1") (pin "1") (pinfunction "1_1") (pintype "power_in"))
      (node (ref "S1") (pin "1") (pinfunction "COMMON_1") (pintype "passive"))
    )
    (net (code "48") (name "Net-(U1A-IN+)") (class "Default")
      (node (ref "J14") (pin "1") (pinfunction "1_1") (pintype "passive"))
      (node (ref "R21") (pin "1") (pinfunction "1_1") (pintype "passive"))
      (node (ref "U1") (pin "3") (pinfunction "IN+_3") (pintype "input"))
    )
    (net (code "49") (name "Net-(U1B-IN+)") (class "Default")
      (node (ref "C13") (pin "1") (pinfunction "1_1") (pintype "passive"))
      (node (ref "R8") (pin "2") (pinfunction "2_2") (pintype "passive"))
      (node (ref "U1") (pin "5") (pinfunction "IN+_5") (pintype "input"))
    )
    (net (code "50") (name "Net-(U2A-IN+)") (class "Default")
      (node (ref "C8") (pin "2") (pinfunction "2_2") (pintype "passive"))
      (node (ref "R15") (pin "2") (pinfunction "2_2") (pintype "passive"))
      (node (ref "U2") (pin "3") (pinfunction "IN+_3") (pintype "input"))
    )
    (net (code "51") (name "Net-(U2A-IN-)") (class "Default")
      (node (ref "C9") (pin "1") (pinfunction "1_1") (pintype "passive"))
      (node (ref "R17") (pin "1") (pinfunction "1_1") (pintype "passive"))
      (node (ref "R18") (pin "1") (pinfunction "1_1") (pintype "passive"))
      (node (ref "U2") (pin "2") (pinfunction "IN-_2") (pintype "input"))
    )
    (net (code "52") (name "Net-(U2B-IN+)") (class "Default")
      (node (ref "C11") (pin "2") (pinfunction "2_2") (pintype "passive"))
      (node (ref "R16") (pin "1") (pinfunction "1_1") (pintype "passive"))
      (node (ref "R20") (pin "2") (pinfunction "2_2") (pintype "passive"))
      (node (ref "U2") (pin "5") (pinfunction "IN+_5") (pintype "input"))
    )
    (net (code "53") (name "Net-(U2B-IN-)") (class "Default")
      (node (ref "C10") (pin "2") (pinfunction "2_2") (pintype "passive"))
      (node (ref "C7") (pin "2") (pinfunction "2_2") (pintype "passive"))
      (node (ref "R14") (pin "2") (pinfunction "2_2") (pintype "passive"))
      (node (ref "R19") (pin "1") (pinfunction "1_1") (pintype "passive"))
      (node (ref "U2") (pin "6") (pinfunction "IN-_6") (pintype "input"))
    )
    (net (code "54") (name "Net-(U2B-OUT)") (class "Default")
      (node (ref "C7") (pin "1") (pinfunction "1_1") (pintype "passive"))
      (node (ref "R14") (pin "1") (pinfunction "1_1") (pintype "passive"))
      (node (ref "R17") (pin "2") (pinfunction "2_2") (pintype "passive"))
      (node (ref "U2") (pin "7") (pinfunction "OUT_7") (pintype "output"))
    )
    (net (code "55") (name "unconnected-(MD1-PB0{slash}PCINT0-Pad24)") (class "Default")
      (node (ref "MD1") (pin "24") (pinfunction "PB0/PCINT0_24") (pintype "passive"))
    )
    (net (code "56") (name "unconnected-(MD1-PD0{slash}D21{slash}SCL{slash}INT0-Pad18)") (class "Default")
      (node (ref "MD1") (pin "18") (pinfunction "PD0/D21/SCL/INT0_18") (pintype "passive"))
    )
    (net (code "57") (name "unconnected-(MD1-PD1{slash}D20{slash}SDA{slash}INT1-Pad17)") (class "Default")
      (node (ref "MD1") (pin "17") (pinfunction "PD1/D20/SDA/INT1_17") (pintype "passive"))
    )
    (net (code "58") (name "unconnected-(MD1-PD2{slash}D19{slash}RXD1{slash}INT2-Pad16)") (class "Default")
      (node (ref "MD1") (pin "16") (pinfunction "PD2/D19/RXD1/INT2_16") (pintype "passive"))
    )
    (net (code "59") (name "unconnected-(MD1-PD3{slash}D18{slash}TXD1{slash}INT3-Pad15)") (class "Default")
      (node (ref "MD1") (pin "15") (pinfunction "PD3/D18/TXD1/INT3_15") (pintype "passive"))
    )
    (net (code "60") (name "unconnected-(MD1-PE0{slash}D0{slash}RXD0-Pad4)") (class "Default")
      (node (ref "MD1") (pin "4") (pinfunction "PE0/D0/RXD0_4") (pintype "passive"))
    )
    (net (code "61") (name "unconnected-(MD1-PE1{slash}D1{slash}TXD0-Pad5)") (class "Default")
      (node (ref "MD1") (pin "5") (pinfunction "PE1/D1/TXD0_5") (pintype "passive"))
    )
    (net (code "62") (name "unconnected-(MD1-PE3{slash}D5{slash}PWM-Pad6)") (class "Default")
      (node (ref "MD1") (pin "6") (pinfunction "PE3/D5/PWM_6") (pintype "passive"))
    )
    (net (code "63") (name "unconnected-(MD1-PE4{slash}D2{slash}PWM{slash}INT4-Pad7)") (class "Default")
      (node (ref "MD1") (pin "7") (pinfunction "PE4/D2/PWM/INT4_7") (pintype "passive"))
    )
    (net (code "64") (name "unconnected-(MD1-PE5{slash}D3{slash}PWM{slash}INT5-Pad8)") (class "Default")
      (node (ref "MD1") (pin "8") (pinfunction "PE5/D3/PWM/INT5_8") (pintype "passive"))
    )
    (net (code "65") (name "unconnected-(MD1-PE6{slash}INT6-Pad9)") (class "Default")
      (node (ref "MD1") (pin "9") (pinfunction "PE6/INT6_9") (pintype "passive"))
    )
    (net (code "66") (name "unconnected-(MD1-PE6{slash}INT7-Pad10)") (class "Default")
      (node (ref "MD1") (pin "10") (pinfunction "PE6/INT7_10") (pintype "passive"))
    )
    (net (code "67") (name "unconnected-(MD1-PF0{slash}D54{slash}A0{slash}ADC0-Pad97)") (class "Default")
      (node (ref "MD1") (pin "97") (pinfunction "PF0/D54/A0/ADC0_97") (pintype "passive"))
    )
    (net (code "68") (name "unconnected-(MD1-PF1{slash}D55{slash}A1{slash}ADC1-Pad96)") (class "Default")
      (node (ref "MD1") (pin "96") (pinfunction "PF1/D55/A1/ADC1_96") (pintype "passive"))
    )
    (net (code "69") (name "unconnected-(MD1-PF7{slash}ADC7{slash}A7{slash}D61{slash}PCINT15-Pad52)") (class "Default")
      (node (ref "MD1") (pin "52") (pinfunction "PF7/ADC7/A7/D61/PCINT15_52") (pintype "passive"))
    )
    (net (code "70") (name "unconnected-(MD1-PH0{slash}D17{slash}RXD2-Pad14)") (class "Default")
      (node (ref "MD1") (pin "14") (pinfunction "PH0/D17/RXD2_14") (pintype "passive"))
    )
    (net (code "71") (name "unconnected-(MD1-PH2{slash}D58{slash}XCK2{slash}TX3-Pad19)") (class "Default")
      (node (ref "MD1") (pin "19") (pinfunction "PH2/D58/XCK2/TX3_19") (pintype "passive"))
    )
    (net (code "72") (name "unconnected-(MD1-PH3{slash}D6{slash}OC4A{slash}PWM-Pad20)") (class "Default")
      (node (ref "MD1") (pin "20") (pinfunction "PH3/D6/OC4A/PWM_20") (pintype "passive"))
    )
    (net (code "73") (name "unconnected-(MD1-PH4{slash}D7{slash}OC4B{slash}TX2{slash}PWM-Pad21)") (class "Default")
      (node (ref "MD1") (pin "21") (pinfunction "PH4/D7/OC4B/TX2/PWM_21") (pintype "passive"))
    )
    (net (code "74") (name "unconnected-(MD1-PH5{slash}D8{slash}OC4C{slash}RX2{slash}PWM-Pad22)") (class "Default")
      (node (ref "MD1") (pin "22") (pinfunction "PH5/D8/OC4C/RX2/PWM_22") (pintype "passive"))
    )
    (net (code "75") (name "unconnected-(MD1-PH6{slash}D9{slash}OC2B{slash}TX1{slash}PWM-Pad23)") (class "Default")
      (node (ref "MD1") (pin "23") (pinfunction "PH6/D9/OC2B/TX1/PWM_23") (pintype "passive"))
    )
    (net (code "76") (name "unconnected-(MD1-PH7{slash}D60{slash}T4-Pad37)") (class "Default")
      (node (ref "MD1") (pin "37") (pinfunction "PH7/D60/T4_37") (pintype "passive"))
    )
    (net (code "77") (name "unconnected-(MD1-PJ0{slash}D15{slash}RXD3{slash}PCINT9-Pad12)") (class "Default")
      (node (ref "MD1") (pin "12") (pinfunction "PJ0/D15/RXD3/PCINT9_12") (pintype "passive"))
    )
    (net (code "78") (name "unconnected-(MD1-PJ1{slash}D14{slash}TXD3{slash}PCINT10-Pad11)") (class "Default")
      (node (ref "MD1") (pin "11") (pinfunction "PJ1/D14/TXD3/PCINT10_11") (pintype "passive"))
    )
    (net (code "79") (name "unconnected-(MD1-PK0{slash}ADC8{slash}A8PCINT16-Pad51)") (class "Default")
      (node (ref "MD1") (pin "51") (pinfunction "PK0/ADC8/A8PCINT16_51") (pintype "passive"))
    )
    (net (code "80") (name "unconnected-(MD1-PK1{slash}ADC9{slash}A9{slash}PCINT17-Pad54)") (class "Default")
      (node (ref "MD1") (pin "54") (pinfunction "PK1/ADC9/A9/PCINT17_54") (pintype "passive"))
    )
    (net (code "81") (name "unconnected-(MD1-PK2{slash}ADC10{slash}A10{slash}PCINT18-Pad53)") (class "Default")
      (node (ref "MD1") (pin "53") (pinfunction "PK2/ADC10/A10/PCINT18_53") (pintype "passive"))
    )
    (net (code "82") (name "unconnected-(MD1-PK3{slash}ADC11{slash}A11{slash}PCINT19-Pad56)") (class "Default")
      (node (ref "MD1") (pin "56") (pinfunction "PK3/ADC11/A11/PCINT19_56") (pintype "passive"))
    )
    (net (code "83") (name "unconnected-(MD1-PK4{slash}ADC12{slash}A12{slash}PCINT20-Pad55)") (class "Default")
      (node (ref "MD1") (pin "55") (pinfunction "PK4/ADC12/A12/PCINT20_55") (pintype "passive"))
    )
    (net (code "84") (name "unconnected-(MD1-PK5{slash}ADC13{slash}A13{slash}PCINT23-Pad58)") (class "Default")
      (node (ref "MD1") (pin "58") (pinfunction "PK5/ADC13/A13/PCINT23_58") (pintype "passive"))
    )
    (net (code "85") (name "unconnected-(MD1-PK6{slash}ADC14{slash}A14{slash}PCINT22-Pad57)") (class "Default")
      (node (ref "MD1") (pin "57") (pinfunction "PK6/ADC14/A14/PCINT22_57") (pintype "passive"))
    )
    (net (code "86") (name "unconnected-(MD1-Pad32)") (class "Default")
      (node (ref "MD1") (pin "32") (pinfunction "32_32") (pintype "passive"))
    )
    (net (code "87") (name "unconnected-(MD1-Pad33)") (class "Default")
      (node (ref "MD1") (pin "33") (pinfunction "33_33") (pintype "passive"))
    )
    (net (code "88") (name "unconnected-(MD1-Pad34)") (class "Default")
      (node (ref "MD1") (pin "34") (pinfunction "34_34") (pintype "passive"))
    )
    (net (code "89") (name "unconnected-(MD1-Pad35)") (class "Default")
      (node (ref "MD1") (pin "35") (pinfunction "35_35") (pintype "passive"))
    )
    (net (code "90") (name "unconnected-(MD1-Pad36)") (class "Default")
      (node (ref "MD1") (pin "36") (pinfunction "36_36") (pintype "passive"))
    )
    (net (code "91") (name "unconnected-(MD1-Pad38)") (class "Default")
      (node (ref "MD1") (pin "38") (pinfunction "38_38") (pintype "passive"))
    )
    (net (code "92") (name "unconnected-(MD1-Pad45)") (class "Default")
      (node (ref "MD1") (pin "45") (pinfunction "45_45") (pintype "passive"))
    )
    (net (code "93") (name "unconnected-(MD1-Pad46)") (class "Default")
      (node (ref "MD1") (pin "46") (pinfunction "46_46") (pintype "passive"))
    )
    (net (code "94") (name "unconnected-(MD1-Pad49)") (class "Default")
      (node (ref "MD1") (pin "49") (pinfunction "49_49") (pintype "passive"))
    )
    (net (code "95") (name "unconnected-(MD1-Pad50)") (class "Default")
      (node (ref "MD1") (pin "50") (pinfunction "50_50") (pintype "passive"))
    )
    (net (code "96") (name "unconnected-(MD1-Pad63)") (class "Default")
      (node (ref "MD1") (pin "63") (pinfunction "63_63") (pintype "passive"))
    )
    (net (code "97") (name "unconnected-(MD1-Pad64)") (class "Default")
      (node (ref "MD1") (pin "64") (pinfunction "64_64") (pintype "passive"))
    )
    (net (code "98") (name "unconnected-(MD1-Pad65)") (class "Default")
      (node (ref "MD1") (pin "65") (pinfunction "65_65") (pintype "passive"))
    )
    (net (code "99") (name "unconnected-(MD1-Pad66)") (class "Default")
      (node (ref "MD1") (pin "66") (pinfunction "66_66") (pintype "passive"))
    )
    (net (code "100") (name "unconnected-(MD1-Pad67)") (class "Default")
      (node (ref "MD1") (pin "67") (pinfunction "67_67") (pintype "passive"))
    )
    (net (code "101") (name "unconnected-(MD1-Pad68)") (class "Default")
      (node (ref "MD1") (pin "68") (pinfunction "68_68") (pintype "passive"))
    )
    (net (code "102") (name "unconnected-(MD1-Pad69)") (class "Default")
      (node (ref "MD1") (pin "69") (pinfunction "69_69") (pintype "passive"))
    )
    (net (code "103") (name "unconnected-(MD1-Pad70)") (class "Default")
      (node (ref "MD1") (pin "70") (pinfunction "70_70") (pintype "passive"))
    )
    (net (code "104") (name "unconnected-(MD1-Pad71)") (class "Default")
      (node (ref "MD1") (pin "71") (pinfunction "71_71") (pintype "passive"))
    )
    (net (code "105") (name "unconnected-(MD1-Pad72)") (class "Default")
      (node (ref "MD1") (pin "72") (pinfunction "72_72") (pintype "passive"))
    )
    (net (code "106") (name "unconnected-(MD1-Pad73)") (class "Default")
      (node (ref "MD1") (pin "73") (pinfunction "73_73") (pintype "passive"))
    )
    (net (code "107") (name "unconnected-(MD1-Pad74)") (class "Default")
      (node (ref "MD1") (pin "74") (pinfunction "74_74") (pintype "passive"))
    )
    (net (code "108") (name "unconnected-(MD1-Pad83)") (class "Default")
      (node (ref "MD1") (pin "83") (pinfunction "83_83") (pintype "passive"))
    )
    (net (code "109") (name "unconnected-(MD1-Pad84)") (class "Default")
      (node (ref "MD1") (pin "84") (pinfunction "84_84") (pintype "passive"))
    )
    (net (code "110") (name "unconnected-(MD1-Pad85)") (class "Default")
      (node (ref "MD1") (pin "85") (pinfunction "85_85") (pintype "passive"))
    )
    (net (code "111") (name "unconnected-(MD1-Pad86)") (class "Default")
      (node (ref "MD1") (pin "86") (pinfunction "86_86") (pintype "passive"))
    )
    (net (code "112") (name "unconnected-(MD1-Pad87)") (class "Default")
      (node (ref "MD1") (pin "87") (pinfunction "87_87") (pintype "passive"))
    )
    (net (code "113") (name "unconnected-(MD1-Pad88)") (class "Default")
      (node (ref "MD1") (pin "88") (pinfunction "88_88") (pintype "passive"))
    )
    (net (code "114") (name "unconnected-(MD1-Pad89)") (class "Default")
      (node (ref "MD1") (pin "89") (pinfunction "89_89") (pintype "passive"))
    )
    (net (code "115") (name "unconnected-(MD1-Pad90)") (class "Default")
      (node (ref "MD1") (pin "90") (pinfunction "90_90") (pintype "passive"))
    )
    (net (code "116") (name "unconnected-(MD1-Pad91)") (class "Default")
      (node (ref "MD1") (pin "91") (pinfunction "91_91") (pintype "passive"))
    )
    (net (code "117") (name "unconnected-(MD1-Pad92)") (class "Default")
      (node (ref "MD1") (pin "92") (pinfunction "92_92") (pintype "passive"))
    )
    (net (code "118") (name "unconnected-(MD1-Pad93)") (class "Default")
      (node (ref "MD1") (pin "93") (pinfunction "93_93") (pintype "passive"))
    )
    (net (code "119") (name "unconnected-(MD1-Pad94)") (class "Default")
      (node (ref "MD1") (pin "94") (pinfunction "94_94") (pintype "passive"))
    )
    (net (code "120") (name "unconnected-(MD1-Pad95)") (class "Default")
      (node (ref "MD1") (pin "95") (pinfunction "95_95") (pintype "passive"))
    )
    (net (code "121") (name "unconnected-(MD1-Pad98)") (class "Default")
      (node (ref "MD1") (pin "98") (pinfunction "98_98") (pintype "passive"))
    )
    (net (code "122") (name "unconnected-(R22-BOT-Pad3)") (class "Default")
      (node (ref "R22") (pin "3") (pinfunction "BOT_3") (pintype "passive"))
    )
    (net (code "123") (name "unconnected-(R24-TOP-Pad3)") (class "Default")
      (node (ref "R24") (pin "3") (pinfunction "TOP_3") (pintype "passive"))
    )
    (net (code "124") (name "unconnected-(S2-A4-Pad4)") (class "Default")
      (node (ref "S2") (pin "4") (pinfunction "A4_4") (pintype "passive"))
    )
    (net (code "125") (name "unconnected-(TFT1-T_CLK-Pad5)") (class "Default")
      (node (ref "TFT1") (pin "5") (pinfunction "T_CLK_5") (pintype "passive"))
    )
    (net (code "126") (name "unconnected-(TFT1-T_CS-Pad4)") (class "Default")
      (node (ref "TFT1") (pin "4") (pinfunction "T_CS_4") (pintype "passive"))
    )
    (net (code "127") (name "unconnected-(TFT1-T_DIN-Pad3)") (class "Default")
      (node (ref "TFT1") (pin "3") (pinfunction "T_DIN_3") (pintype "passive"))
    )
    (net (code "128") (name "unconnected-(TFT1-T_DO-Pad2)") (class "Default")
      (node (ref "TFT1") (pin "2") (pinfunction "T_DO_2") (pintype "passive"))
    )
    (net (code "129") (name "unconnected-(TFT1-T_IRQ-Pad1)") (class "Default")
      (node (ref "TFT1") (pin "1") (pinfunction "T_IRQ_1") (pintype "passive"))
    )
  )
)
